# AST1004.net
KiCad netlist of a schematic drawn in EAGLE
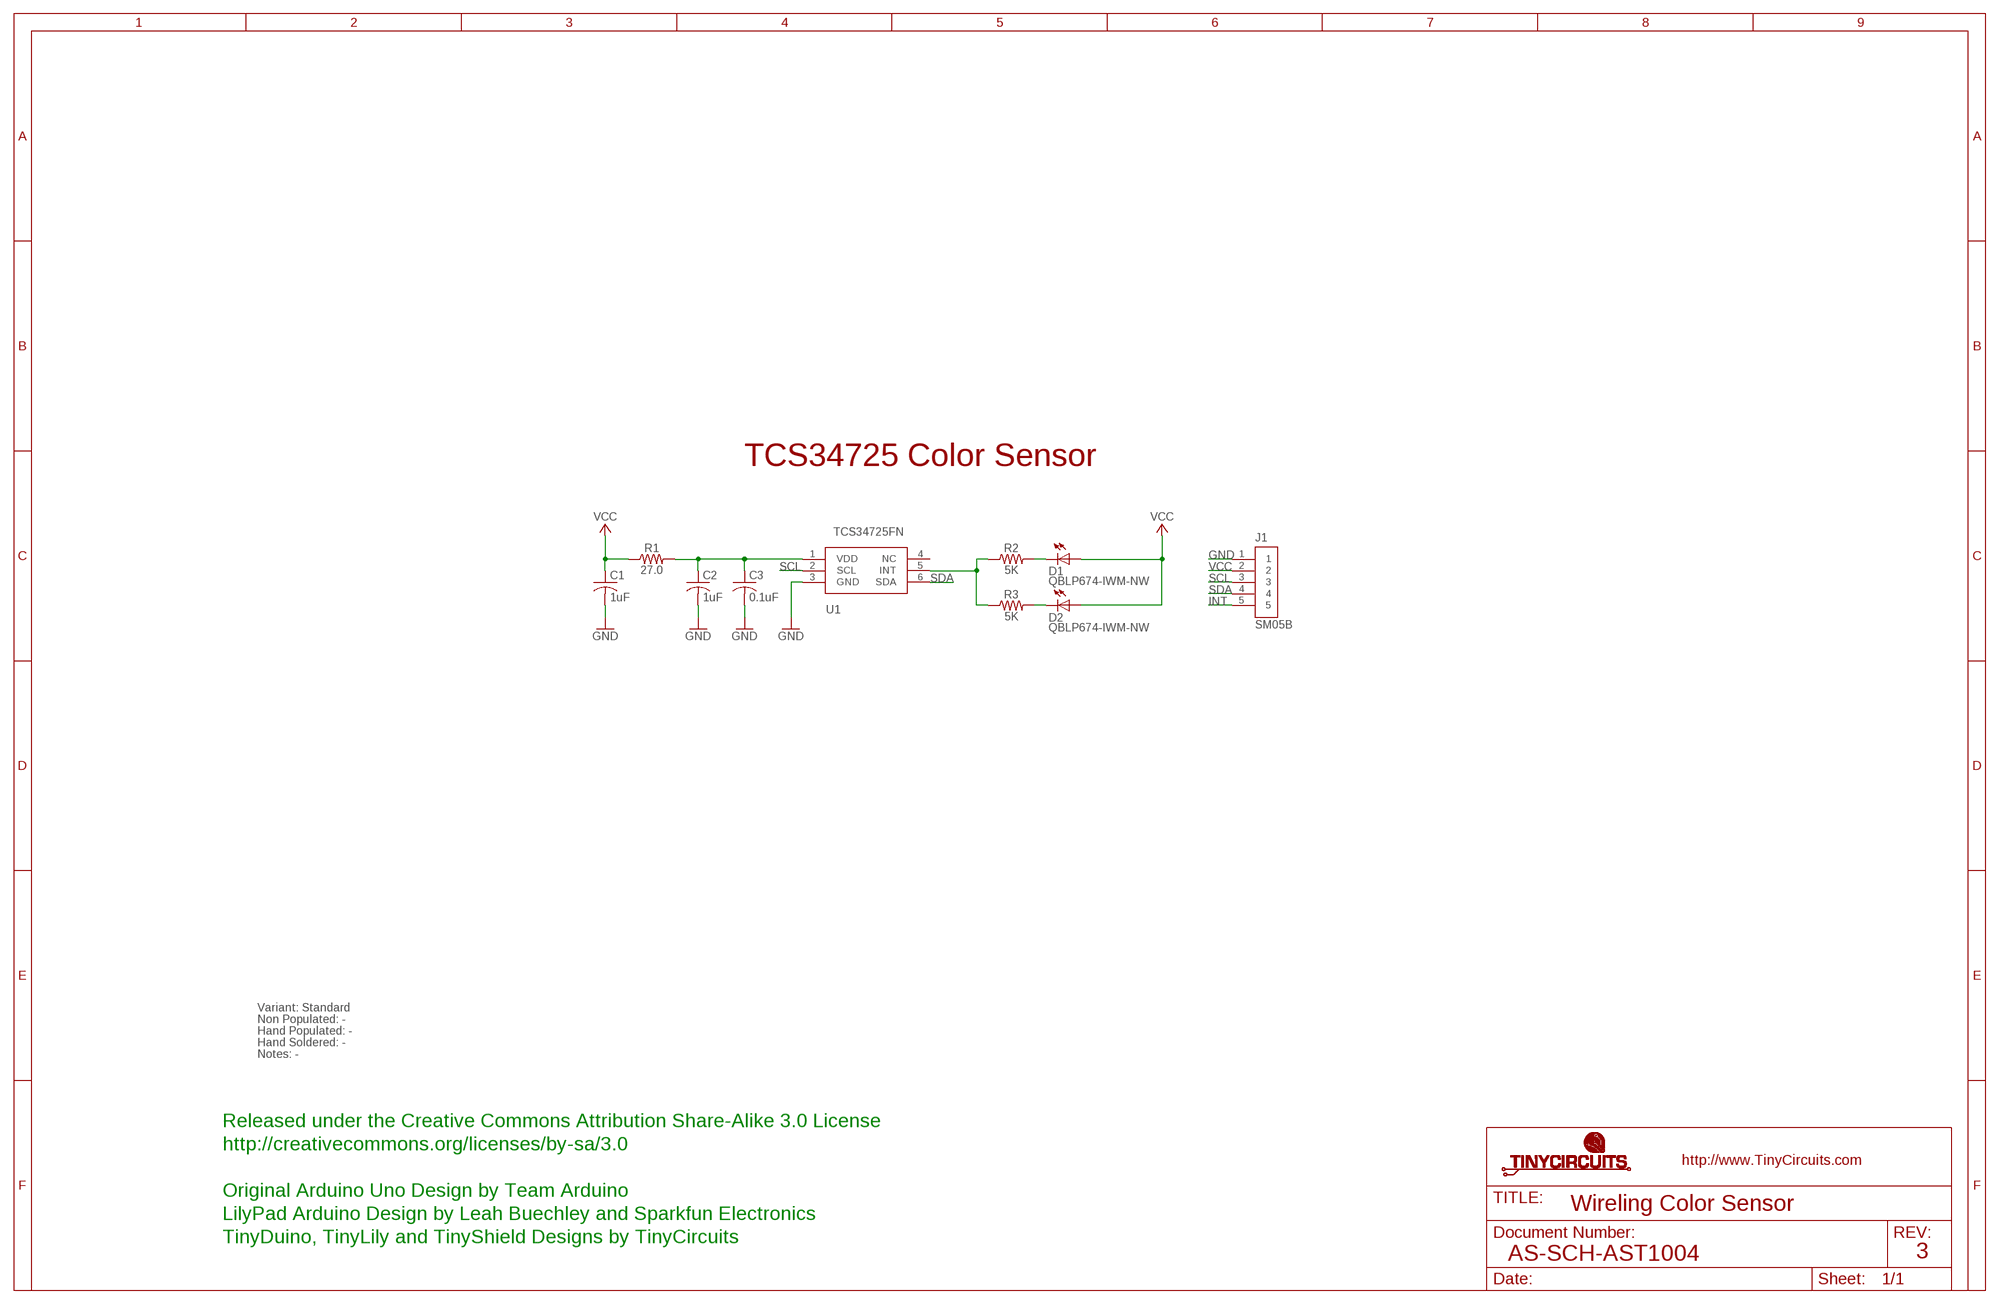
[diagram p0: schematic, sheet 1]

(export (version "E")
  (design (tool "Eeschema 10.0.6"))
  (components
    (comp (ref "C1")
      (value "1uF")
      (footprint "eagle-import:C0402")
      (fields (field (name "PARTNO") "AS-ITM-00105") (field (name "PARTNO_1") "AS-ITM-00105"))
      (libsource (lib "eagle-import") (part "AS-ITM-00105"))
    )
    (comp (ref "C2")
      (value "1uF")
      (footprint "eagle-import:C0402")
      (fields (field (name "PARTNO") "AS-ITM-00105") (field (name "PARTNO_1") "AS-ITM-00105"))
      (libsource (lib "eagle-import") (part "AS-ITM-00105"))
    )
    (comp (ref "C3")
      (value "0.1uF")
      (footprint "eagle-import:C0402")
      (fields (field (name "PARTNO") "AS-ITM-00008"))
      (libsource (lib "eagle-import") (part "AS-ITM-00008"))
    )
    (comp (ref "D1")
      (value "QBLP674-IWM-NW")
      (footprint "eagle-import:LED_TOP_2.8X1.4")
      (fields (field (name "PARTNO") "AS-ITM-00554") (field (name "PARTNO_1") "AS-ITM-00554"))
      (libsource (lib "eagle-import") (part "AS-ITM-00554"))
    )
    (comp (ref "D2")
      (value "QBLP674-IWM-NW")
      (footprint "eagle-import:LED_TOP_2.8X1.4")
      (fields (field (name "PARTNO") "AS-ITM-00554") (field (name "PARTNO_1") "AS-ITM-00554"))
      (libsource (lib "eagle-import") (part "AS-ITM-00554"))
    )
    (comp (ref "J1")
      (value "SM05B")
      (footprint "eagle-import:JST_SH_5X1_EDGE")
      (fields (field (name "PARTNO") "AS-ITM-00340"))
      (libsource (lib "eagle-import") (part "AS-ITM-00340EDGE"))
    )
    (comp (ref "R1")
      (value "27.0")
      (footprint "eagle-import:0402")
      (fields (field (name "PARTNO") "AS-ITM-00240"))
      (libsource (lib "eagle-import") (part "AS-ITM-00240"))
    )
    (comp (ref "R2")
      (value "5K")
      (footprint "eagle-import:0402")
      (fields (field (name "PARTNO") "AS-ITM-00289"))
      (libsource (lib "eagle-import") (part "AS-ITM-00289"))
    )
    (comp (ref "R3")
      (value "5K")
      (footprint "eagle-import:0402")
      (fields (field (name "PARTNO") "AS-ITM-00289"))
      (libsource (lib "eagle-import") (part "AS-ITM-00289"))
    )
    (comp (ref "U1")
      (value "TCS34725FN")
      (footprint "eagle-import:TSL2572")
      (fields (field (name "PARTNO") "AS-ITM-00140") (field (name "PARTNO_1") "AS-ITM-00140"))
      (libsource (lib "eagle-import") (part "AS-ITM-00140"))
    )
  )
  (nets
    (net (code "1") (name "/INT") (class "Default")
      (node (ref "J1") (pin "5") (pinfunction "5_5") (pintype "bidirectional"))
    )
    (net (code "2") (name "/SCL") (class "Default")
      (node (ref "J1") (pin "3") (pinfunction "3_3") (pintype "bidirectional"))
      (node (ref "U1") (pin "2") (pinfunction "SCL_2") (pintype "bidirectional"))
    )
    (net (code "3") (name "/SDA") (class "Default")
      (node (ref "J1") (pin "4") (pinfunction "4_4") (pintype "bidirectional"))
      (node (ref "U1") (pin "6") (pinfunction "SDA_6") (pintype "bidirectional"))
    )
    (net (code "4") (name "GND") (class "Default")
      (node (ref "C1") (pin "2") (pinfunction "2_2") (pintype "passive"))
      (node (ref "C2") (pin "2") (pinfunction "2_2") (pintype "passive"))
      (node (ref "C3") (pin "2") (pinfunction "2_2") (pintype "passive"))
      (node (ref "J1") (pin "1") (pinfunction "1_1") (pintype "bidirectional"))
      (node (ref "U1") (pin "3") (pinfunction "GND_3") (pintype "bidirectional"))
    )
    (net (code "5") (name "Net-(D1-PadC)") (class "Default")
      (node (ref "D1") (pin "C") (pinfunction "C_C") (pintype "passive"))
      (node (ref "R2") (pin "2") (pinfunction "2_2") (pintype "passive"))
    )
    (net (code "6") (name "Net-(D2-PadC)") (class "Default")
      (node (ref "D2") (pin "C") (pinfunction "C_C") (pintype "passive"))
      (node (ref "R3") (pin "2") (pinfunction "2_2") (pintype "passive"))
    )
    (net (code "7") (name "Net-(U1-INT)") (class "Default")
      (node (ref "R2") (pin "1") (pinfunction "1_1") (pintype "passive"))
      (node (ref "R3") (pin "1") (pinfunction "1_1") (pintype "passive"))
      (node (ref "U1") (pin "5") (pinfunction "INT_5") (pintype "bidirectional"))
    )
    (net (code "8") (name "Net-(U1-VDD)") (class "Default")
      (node (ref "C2") (pin "1") (pinfunction "1_1") (pintype "passive"))
      (node (ref "C3") (pin "1") (pinfunction "1_1") (pintype "passive"))
      (node (ref "R1") (pin "2") (pinfunction "2_2") (pintype "passive"))
      (node (ref "U1") (pin "1") (pinfunction "VDD_1") (pintype "bidirectional"))
    )
    (net (code "9") (name "VCC") (class "Default")
      (node (ref "C1") (pin "1") (pinfunction "1_1") (pintype "passive"))
      (node (ref "D1") (pin "A") (pinfunction "A_A") (pintype "passive"))
      (node (ref "D2") (pin "A") (pinfunction "A_A") (pintype "passive"))
      (node (ref "J1") (pin "2") (pinfunction "2_2") (pintype "bidirectional"))
      (node (ref "R1") (pin "1") (pinfunction "1_1") (pintype "passive"))
    )
    (net (code "10") (name "unconnected-(U1-NC-Pad4)") (class "Default")
      (node (ref "U1") (pin "4") (pinfunction "NC_4") (pintype "bidirectional"))
    )
  )
)
